# PSU-IO.net
KiCad netlist of a schematic drawn in Altium Designer
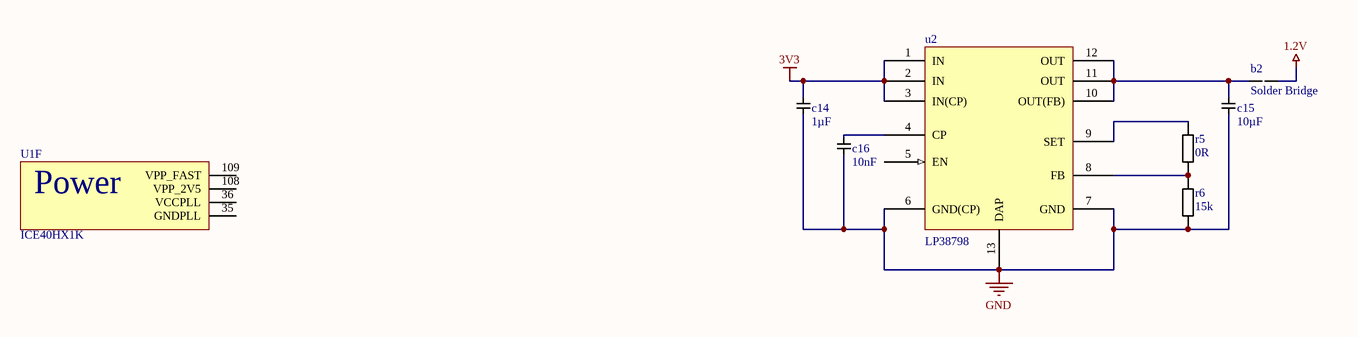
[diagram p0: PSU-IO.SchDoc]

(export (version "E")
  (design (tool "Eeschema 10.0.6"))
  (components
    (comp (ref "b2")
      (value "Solder Bridge")
      (footprint "Solder Bridge")
      (libsource (lib "Board_Props") (part "Solder Bridge"))
    )
    (comp (ref "c14")
      (value "1µF")
      (footprint "1206")
      (description "...F")
      (libsource (lib "Generic R-C") (part "1206 Cap"))
    )
    (comp (ref "c15")
      (value "10µF")
      (footprint "1206")
      (description "...F")
      (libsource (lib "Generic R-C") (part "1206 Cap"))
    )
    (comp (ref "c16")
      (value "10nF")
      (footprint "0603")
      (description "...F")
      (libsource (lib "Generic R-C") (part "0603 Capacitor"))
    )
    (comp (ref "r5")
      (value "0R")
      (footprint "0603")
      (description "...R")
      (libsource (lib "Generic R-C") (part "0603 Resistor"))
    )
    (comp (ref "r6")
      (value "15k")
      (footprint "0603")
      (description "...R")
      (libsource (lib "Generic R-C") (part "0603 Resistor"))
    )
    (comp (ref "U1")
      (value "ICE40HX1K")
      (footprint "TQFP-144")
      (description "ICE40 FPGA TQFP-144")
      (libsource (lib "Lattice") (part "ICE40HX1K"))
    )
    (comp (ref "u2")
      (value "LP38798")
      (footprint "WSON-12_4X4")
      (description "800mA Ulta-Low-Noise, High-PSRR LDO")
      (libsource (lib "Texas Instruments") (part "LP38798"))
    )
  )
  (nets
    (net (code "1") (name "1.2V") (class "Default")
      (node (ref "b2") (pin "2") (pinfunction "2_2") (pintype "passive"))
    )
    (net (code "2") (name "3V3") (class "Default")
      (node (ref "c14") (pin "2") (pinfunction "2_2") (pintype "passive"))
      (node (ref "u2") (pin "1") (pinfunction "IN_1") (pintype "power_in"))
      (node (ref "u2") (pin "2") (pinfunction "IN_2") (pintype "power_in"))
      (node (ref "u2") (pin "3") (pinfunction "IN(CP)_3") (pintype "power_in"))
    )
    (net (code "3") (name "GND") (class "Default")
      (node (ref "c14") (pin "1") (pinfunction "1_1") (pintype "passive"))
      (node (ref "c15") (pin "1") (pinfunction "1_1") (pintype "passive"))
      (node (ref "c16") (pin "1") (pinfunction "1_1") (pintype "passive"))
      (node (ref "r6") (pin "1") (pintype "passive"))
      (node (ref "u2") (pin "13") (pinfunction "DAP_13") (pintype "power_in"))
      (node (ref "u2") (pin "6") (pinfunction "GND(CP)_6") (pintype "power_in"))
      (node (ref "u2") (pin "7") (pinfunction "GND_7") (pintype "power_in"))
    )
    (net (code "4") (name "Net-(u2-CP)") (class "Default")
      (node (ref "c16") (pin "2") (pinfunction "2_2") (pintype "passive"))
      (node (ref "u2") (pin "4") (pinfunction "CP_4") (pintype "power_in"))
    )
    (net (code "5") (name "Net-(u2-FB)") (class "Default")
      (node (ref "r5") (pin "1") (pintype "passive"))
      (node (ref "r6") (pin "2") (pintype "passive"))
      (node (ref "u2") (pin "8") (pinfunction "FB_8") (pintype "power_in"))
    )
    (net (code "6") (name "Net-(u2-OUT(FB))") (class "Default")
      (node (ref "b2") (pin "1") (pinfunction "1_1") (pintype "passive"))
      (node (ref "c15") (pin "2") (pinfunction "2_2") (pintype "passive"))
      (node (ref "u2") (pin "10") (pinfunction "OUT(FB)_10") (pintype "power_in"))
      (node (ref "u2") (pin "11") (pinfunction "OUT_11") (pintype "power_in"))
      (node (ref "u2") (pin "12") (pinfunction "OUT_12") (pintype "power_in"))
    )
    (net (code "7") (name "Net-(u2-SET)") (class "Default")
      (node (ref "r5") (pin "2") (pintype "passive"))
      (node (ref "u2") (pin "9") (pinfunction "SET_9") (pintype "power_in"))
    )
    (net (code "8") (name "unconnected-(U1F-GNDPLL-Pad35)") (class "Default")
      (node (ref "U1") (pin "35") (pinfunction "GNDPLL_35") (pintype "power_in"))
    )
    (net (code "9") (name "unconnected-(U1F-VCCPLL-Pad36)") (class "Default")
      (node (ref "U1") (pin "36") (pinfunction "VCCPLL_36") (pintype "power_in"))
    )
    (net (code "10") (name "unconnected-(U1F-VPP_2V5-Pad108)") (class "Default")
      (node (ref "U1") (pin "108") (pinfunction "VPP_2V5_108") (pintype "power_in"))
    )
    (net (code "11") (name "unconnected-(U1F-VPP_FAST-Pad109)") (class "Default")
      (node (ref "U1") (pin "109") (pinfunction "VPP_FAST_109") (pintype "power_in"))
    )
    (net (code "12") (name "unconnected-(u2-EN-Pad5)") (class "Default")
      (node (ref "u2") (pin "5") (pinfunction "EN_5") (pintype "input"))
    )
  )
)
